# Power.net
KiCad netlist of a schematic drawn in Altium Designer
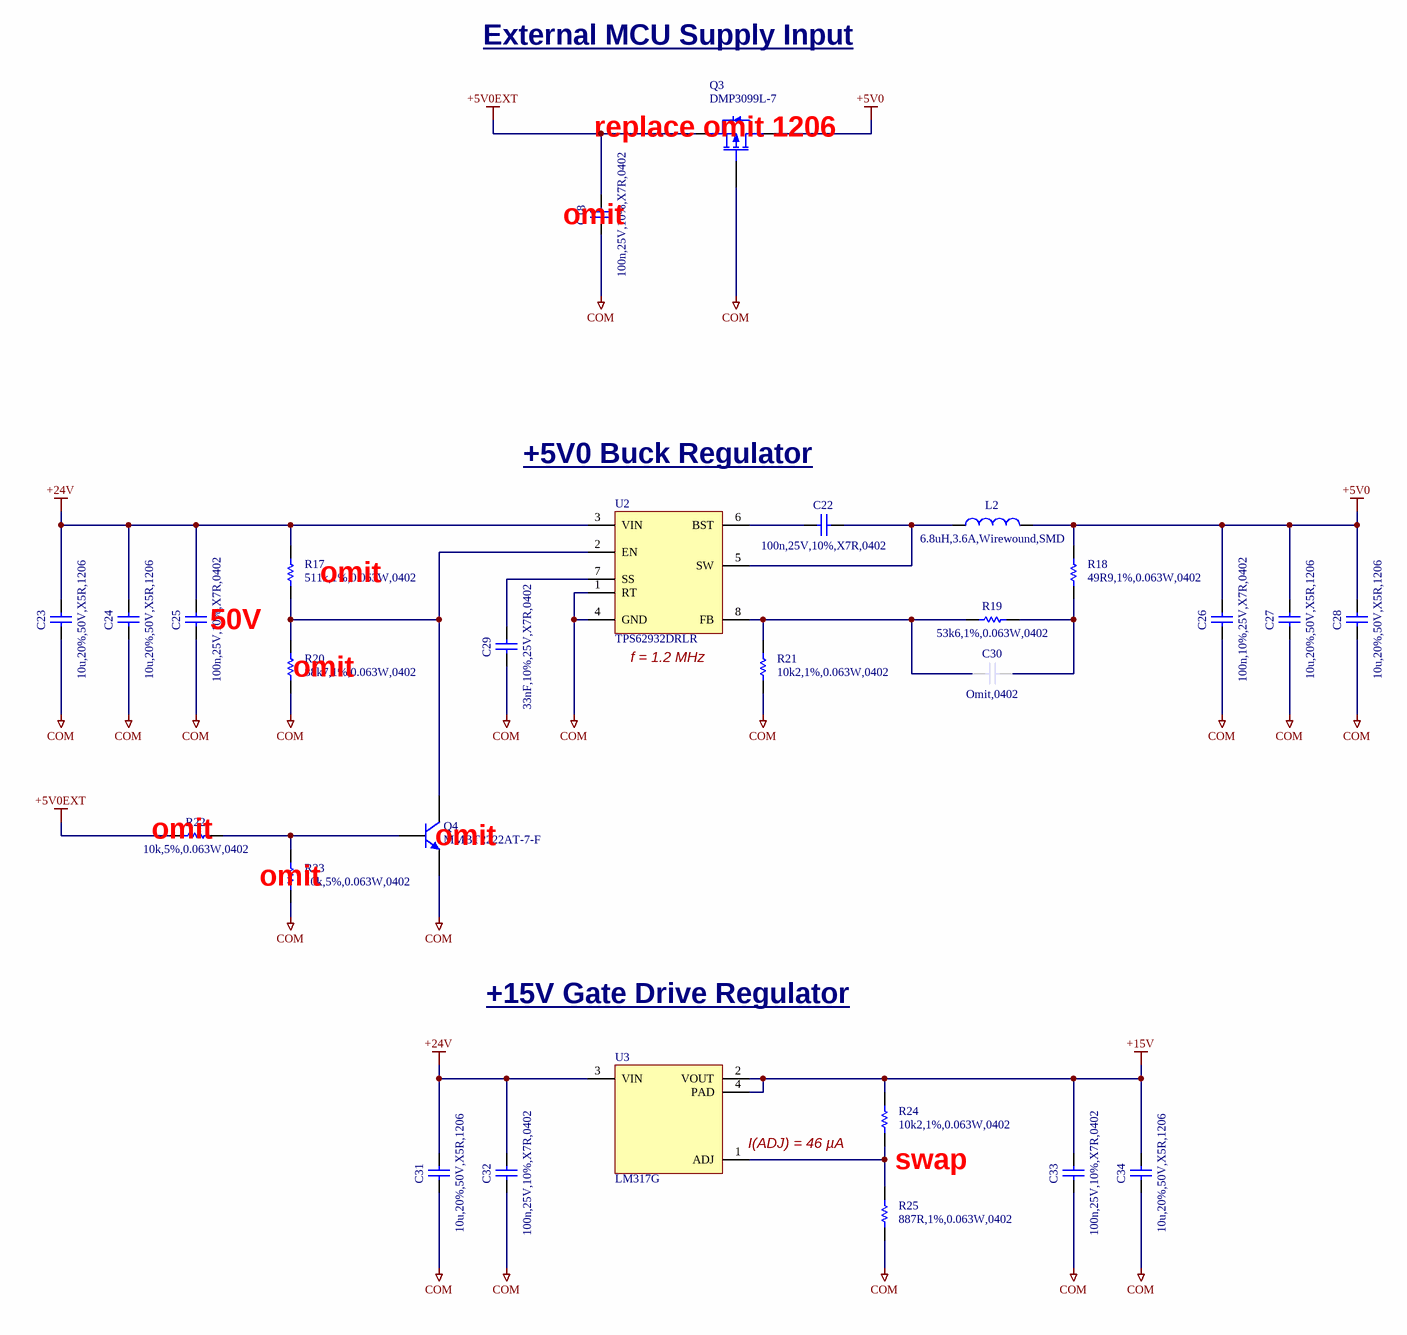
[diagram p0: Power.SchDoc]

(export (version "E")
  (design (tool "Eeschema 10.0.6"))
  (components
    (comp (ref "C18")
      (value "100n,25V,10%,X7R,0402")
      (footprint "CAPC1005X06N")
      (description "0.1ï¿½F ï¿½10% 25V Ceramic Capacitor X7R 0402 (1005 Metric)")
      (fields
        (field (name "MANUFACTURER 1 PART NUMBER") "GRM155R71E104KE14J")
        (field (name "VENDOR 1 PART NUMBER") "490-14603-1-ND")
        (field (name "CREATEDBY") "Judd Foster")
      )
      (libsource (lib "Component Library") (part "CAP,Cer,100nF,10%,25VDC,X7R,0402"))
    )
    (comp (ref "C22")
      (value "100n,25V,10%,X7R,0402")
      (footprint "CAPC1005X06N")
      (description "0.1ï¿½F ï¿½10% 25V Ceramic Capacitor X7R 0402 (1005 Metric)")
      (fields
        (field (name "MANUFACTURER 1 PART NUMBER") "GRM155R71E104KE14J")
        (field (name "VENDOR 1 PART NUMBER") "490-14603-1-ND")
        (field (name "CREATEDBY") "Judd Foster")
      )
      (libsource (lib "Component Library") (part "CAP,Cer,100nF,10%,25VDC,X7R,0402"))
    )
    (comp (ref "C23")
      (value "10u,20%,50V,X5R,1206")
      (footprint "CAPC3216X16N")
      (description "10ï¿½F ï¿½20% 50V Ceramic Capacitor X5R 1206 (3216 Metric)")
      (fields
        (field (name "MANUFACTURER 1 PART NUMBER") "CL31A106MBHNNNE")
        (field (name "VENDOR 1 PART NUMBER") "1276-6736-1-ND")
        (field (name "CREATEDBY") "Judd Foster")
      )
      (libsource (lib "Component Library") (part "CAP,Cer,10uF,50VDC,X5R,1206"))
    )
    (comp (ref "C24")
      (value "10u,20%,50V,X5R,1206")
      (footprint "CAPC3216X16N")
      (description "10ï¿½F ï¿½20% 50V Ceramic Capacitor X5R 1206 (3216 Metric)")
      (fields
        (field (name "MANUFACTURER 1 PART NUMBER") "CL31A106MBHNNNE")
        (field (name "VENDOR 1 PART NUMBER") "1276-6736-1-ND")
        (field (name "CREATEDBY") "Judd Foster")
      )
      (libsource (lib "Component Library") (part "CAP,Cer,10uF,50VDC,X5R,1206"))
    )
    (comp (ref "C25")
      (value "100n,25V,10%,X7R,0402")
      (footprint "CAPC1005X06N")
      (description "0.1ï¿½F ï¿½10% 25V Ceramic Capacitor X7R 0402 (1005 Metric)")
      (fields
        (field (name "MANUFACTURER 1 PART NUMBER") "GRM155R71E104KE14J")
        (field (name "VENDOR 1 PART NUMBER") "490-14603-1-ND")
        (field (name "CREATEDBY") "Judd Foster")
      )
      (libsource (lib "Component Library") (part "CAP,Cer,100nF,10%,25VDC,X7R,0402"))
    )
    (comp (ref "C26")
      (value "100n,10%,25V,X7R,0402")
      (footprint "CAPC1005X06N")
      (description "0.1ï¿½F ï¿½10% 25V Ceramic Capacitor X7R 0402 (1005 Metric)")
      (fields
        (field (name "MANUFACTURER 1 PART NUMBER") "GRM155R71E104KE14J")
        (field (name "VENDOR 1 PART NUMBER") "490-14603-1-ND")
        (field (name "CREATEDBY") "Judd Foster")
      )
      (libsource (lib "Component Library") (part "CAP,Cer,100nF,10%,25V,X7R,0402"))
    )
    (comp (ref "C27")
      (value "10u,20%,50V,X5R,1206")
      (footprint "CAPC3216X16N")
      (description "10ï¿½F ï¿½20% 50V Ceramic Capacitor X5R 1206 (3216 Metric)")
      (fields
        (field (name "MANUFACTURER 1 PART NUMBER") "CL31A106MBHNNNE")
        (field (name "VENDOR 1 PART NUMBER") "1276-6736-1-ND")
        (field (name "CREATEDBY") "Judd Foster")
      )
      (libsource (lib "Component Library") (part "CAP,Cer,10uF,50VDC,X5R,1206"))
    )
    (comp (ref "C28")
      (value "10u,20%,50V,X5R,1206")
      (footprint "CAPC3216X16N")
      (description "10ï¿½F ï¿½20% 50V Ceramic Capacitor X5R 1206 (3216 Metric)")
      (fields
        (field (name "MANUFACTURER 1 PART NUMBER") "CL31A106MBHNNNE")
        (field (name "VENDOR 1 PART NUMBER") "1276-6736-1-ND")
        (field (name "CREATEDBY") "Judd Foster")
      )
      (libsource (lib "Component Library") (part "CAP,Cer,10uF,50VDC,X5R,1206"))
    )
    (comp (ref "C29")
      (value "33nF,10%,25V,X7R,0402")
      (footprint "CAPC1005X06N")
      (description "0.033 ÂµF Â±10% 25V Ceramic Capacitor X7R 0402 (1005 Metric)")
      (fields
        (field (name "MANUFACTURER 1 PART NUMBER") "GRM155R71E333KA88D")
        (field (name "VENDOR 1 PART NUMBER") "490-3253-1-ND")
        (field (name "CREATEDBY") "Judd Foster")
      )
      (libsource (lib "Component Library") (part "CAP,Cer,33nF,10%,25V,X7R,0402"))
    )
    (comp (ref "C30")
      (value "Omit,0402")
      (footprint "CAPC1005X06N")
      (description "Omit")
      (fields (field (name "CREATEDBY") "Judd Foster"))
      (libsource (lib "Component Library") (part "CAP,Omit,0402"))
    )
    (comp (ref "C31")
      (value "10u,20%,50V,X5R,1206")
      (footprint "CAPC3216X16N")
      (description "10ï¿½F ï¿½20% 50V Ceramic Capacitor X5R 1206 (3216 Metric)")
      (fields
        (field (name "MANUFACTURER 1 PART NUMBER") "CL31A106MBHNNNE")
        (field (name "VENDOR 1 PART NUMBER") "1276-6736-1-ND")
        (field (name "CREATEDBY") "Judd Foster")
      )
      (libsource (lib "Component Library") (part "CAP,Cer,10uF,50VDC,X5R,1206"))
    )
    (comp (ref "C32")
      (value "100n,25V,10%,X7R,0402")
      (footprint "CAPC1005X06N")
      (description "0.1ï¿½F ï¿½10% 25V Ceramic Capacitor X7R 0402 (1005 Metric)")
      (fields
        (field (name "MANUFACTURER 1 PART NUMBER") "GRM155R71E104KE14J")
        (field (name "VENDOR 1 PART NUMBER") "490-14603-1-ND")
        (field (name "CREATEDBY") "Judd Foster")
      )
      (libsource (lib "Component Library") (part "CAP,Cer,100nF,10%,25VDC,X7R,0402"))
    )
    (comp (ref "C33")
      (value "100n,25V,10%,X7R,0402")
      (footprint "CAPC1005X06N")
      (description "0.1ï¿½F ï¿½10% 25V Ceramic Capacitor X7R 0402 (1005 Metric)")
      (fields
        (field (name "MANUFACTURER 1 PART NUMBER") "GRM155R71E104KE14J")
        (field (name "VENDOR 1 PART NUMBER") "490-14603-1-ND")
        (field (name "CREATEDBY") "Judd Foster")
      )
      (libsource (lib "Component Library") (part "CAP,Cer,100nF,10%,25VDC,X7R,0402"))
    )
    (comp (ref "C34")
      (value "10u,20%,50V,X5R,1206")
      (footprint "CAPC3216X16N")
      (description "10ï¿½F ï¿½20% 50V Ceramic Capacitor X5R 1206 (3216 Metric)")
      (fields
        (field (name "MANUFACTURER 1 PART NUMBER") "CL31A106MBHNNNE")
        (field (name "VENDOR 1 PART NUMBER") "1276-6736-1-ND")
        (field (name "CREATEDBY") "Judd Foster")
      )
      (libsource (lib "Component Library") (part "CAP,Cer,10uF,50VDC,X5R,1206"))
    )
    (comp (ref "L2")
      (value "6.8uH,3.6A,Wirewound,SMD")
      (footprint "BOURNS_SRN6045TA")
      (description "6.8 ÂµH Semi-Shielded Drum Core, Wirewound Inductor 3.6 A 34mOhm Nonstandard")
      (fields
        (field (name "MANUFACTURER 1 PART NUMBER") "SRN6045TA-6R8M")
        (field (name "VENDOR 1 PART NUMBER") "SRN6045TA-6R8MCT-ND")
        (field (name "CREATEDBY") "Judd Foster")
      )
      (libsource (lib "Component Library") (part "IND,6.8uH,3.6A,Wirewound,SMD"))
    )
    (comp (ref "Q3")
      (value "DMP3099L-7")
      (footprint "DIODES_SOT23")
      (description "P-Channel 30 V 3.8A (Ta) 1.08W (Ta) Surface Mount SOT-23-3")
      (fields
        (field (name "VENDOR 1 PART NUMBER") "DMP3099L-7DICT-ND")
        (field (name "CREATEDBY") "Judd Foster")
      )
      (libsource (lib "Component Library") (part "MOSFET,P Ch,30V,3.8A"))
    )
    (comp (ref "Q4")
      (value "MMBT2222AT-7-F")
      (footprint "SOTFL50P160X90-3N")
      (description "Bipolar (BJT) Transistor NPN 40 V 600 mA 300MHz 150 mW Surface Mount SOT-523")
      (fields
        (field (name "VENDOR 1 PART NUMBER") "MMBT2222AT-FDICT-ND")
        (field (name "CREATEDBY") "Judd Foster")
      )
      (libsource (lib "Component Library") (part "Trans,NPN,40V,600mA,SOT523"))
    )
    (comp (ref "R17")
      (value "511k,1%,0.063W,0402")
      (footprint "RESC1005X04N")
      (description "511 kOhms Â±1% 0.063W, 1/16W Chip Resistor 0402 (1005 Metric) Moisture Resistant Thick Film")
      (fields
        (field (name "MANUFACTURER 1 PART NUMBER") "RC0402FR-07511KL")
        (field (name "VENDOR 1 PART NUMBER") "YAG3176CT-ND")
        (field (name "CREATEDBY") "Judd Foster")
      )
      (libsource (lib "Component Library") (part "RES,511k,1%,0.063W,0402"))
    )
    (comp (ref "R18")
      (value "49R9,1%,0.063W,0402")
      (footprint "RESC1005X04N")
      (description "49.9 Ohms Â±1% 0.063W, 1/16W Chip Resistor 0402 (1005 Metric) Moisture Resistant Thick Film")
      (fields
        (field (name "MANUFACTURER 1 PART NUMBER") "RC0402FR-0749R9L")
        (field (name "VENDOR 1 PART NUMBER") "311-49.9LRCT-ND")
        (field (name "CREATEDBY") "Judd Foster")
      )
      (libsource (lib "Component Library") (part "RES,49R9,1%,0.063W,0402"))
    )
    (comp (ref "R19")
      (value "53k6,1%,0.063W,0402")
      (footprint "RESC1005X04N")
      (description "53.6 kOhms Â±1% 0.063W, 1/16W Chip Resistor 0402 (1005 Metric) Moisture Resistant Thick Film")
      (fields
        (field (name "MANUFACTURER 1 PART NUMBER") "RC0402FR-0753K6L")
        (field (name "VENDOR 1 PART NUMBER") "311-53.6KLRCT-ND")
        (field (name "CREATEDBY") "Judd Foster")
      )
      (libsource (lib "Component Library") (part "RES.53k6,1%,0.063W,0402"))
    )
    (comp (ref "R20")
      (value "88k7,1%,0.063W,0402")
      (footprint "RESC1005X04N")
      (fields
        (field (name "MANUFACTURER 1 PART NUMBER") "AC0402FR-0788K7L")
        (field (name "VENDOR 1 PART NUMBER") "13-AC0402FR-0788K7LCT-ND")
        (field (name "CREATEDBY") "Judd Foster")
      )
      (libsource (lib "Component Library") (part "RES,88k7,1%,0.063W,0402"))
    )
    (comp (ref "R21")
      (value "10k2,1%,0.063W,0402")
      (footprint "RESC1005X04N")
      (description "10.2 kOhms Â±1% 0.063W, 1/16W Chip Resistor 0402 (1005 Metric) Moisture Resistant Thick Film")
      (fields
        (field (name "MANUFACTURER 1 PART NUMBER") "RC0402FR-0710K2L")
        (field (name "VENDOR 1 PART NUMBER") "YAG2950CT-ND")
        (field (name "CREATEDBY") "Judd Foster")
      )
      (libsource (lib "Component Library") (part "RES,10k2,1%,0.063W,0402"))
    )
    (comp (ref "R22")
      (value "10k,5%,0.063W,0402")
      (footprint "RESC1005X04N")
      (description "10 kOhms ï¿½5% 0.063W, 1/16W Chip Resistor 0402 (1005 Metric) Automotive AEC-Q200 Thick Film")
      (fields
        (field (name "MANUFACTURER 1 PART NUMBER") "RMCF0402JT10K0")
        (field (name "VENDOR 1 PART NUMBER") "RMCF0402JT10K0CT-ND")
        (field (name "CREATEDBY") "Judd Foster")
      )
      (libsource (lib "Component Library") (part "RES,10k,5%,0.063W,0402"))
    )
    (comp (ref "R23")
      (value "10k,5%,0.063W,0402")
      (footprint "RESC1005X04N")
      (description "10 kOhms ï¿½5% 0.063W, 1/16W Chip Resistor 0402 (1005 Metric) Automotive AEC-Q200 Thick Film")
      (fields
        (field (name "MANUFACTURER 1 PART NUMBER") "RMCF0402JT10K0")
        (field (name "VENDOR 1 PART NUMBER") "RMCF0402JT10K0CT-ND")
        (field (name "CREATEDBY") "Judd Foster")
      )
      (libsource (lib "Component Library") (part "RES,10k,5%,0.063W,0402"))
    )
    (comp (ref "R24")
      (value "10k2,1%,0.063W,0402")
      (footprint "RESC1005X04N")
      (description "10.2 kOhms Â±1% 0.063W, 1/16W Chip Resistor 0402 (1005 Metric) Moisture Resistant Thick Film")
      (fields
        (field (name "MANUFACTURER 1 PART NUMBER") "RC0402FR-0710K2L")
        (field (name "VENDOR 1 PART NUMBER") "YAG2950CT-ND")
        (field (name "CREATEDBY") "Judd Foster")
      )
      (libsource (lib "Component Library") (part "RES,10k2,1%,0.063W,0402"))
    )
    (comp (ref "R25")
      (value "887R,1%,0.063W,0402")
      (footprint "RESC1005X04N")
      (description "887Î© 62.5mW 50V Â±200ppm/â„ƒ Â±1% Thick Film Resistors 0402 Chip Resistor - Surface Mount ROHS")
      (fields
        (field (name "MANUFACTURER 1 PART NUMBER") "RC-02W8870FT")
        (field (name "VENDOR 1 PART NUMBER") "C321640")
        (field (name "CREATEDBY") "Judd Foster")
      )
      (libsource (lib "Component Library") (part "RES,887R,1%,0.063W,0402"))
    )
    (comp (ref "U2")
      (value "TPS62932DRLR")
      (footprint "TEXASINSTRUMENTS_PKG_DRL0008A")
      (description "Buck Switching Regulator IC Positive Adjustable 0.8V 1 Output 2A SOT-583")
      (fields
        (field (name "VENDOR 1 PART NUMBER") "296-TPS62932DRLRCT-ND")
        (field (name "CREATEDBY") "Judd Foster")
      )
      (libsource (lib "Component Library") (part "TPS62932DRLR"))
    )
    (comp (ref "U3")
      (value "LM317G")
      (footprint "UMW_PKG_SOT223-3L")
      (fields (field (name "VENDOR 1 PART NUMBER") "C347367") (field (name "CREATEDBY") "Judd Foster"))
      (libsource (lib "Component Library") (part "LM317G"))
    )
  )
  (nets
    (net (code "1") (name "+5V0") (class "Default")
      (node (ref "C26") (pin "2") (pinfunction "2_2") (pintype "passive"))
      (node (ref "C27") (pin "2") (pinfunction "2_2") (pintype "passive"))
      (node (ref "C28") (pin "2") (pinfunction "2_2") (pintype "passive"))
      (node (ref "L2") (pin "2") (pinfunction "2_2") (pintype "passive"))
      (node (ref "Q3") (pin "3") (pinfunction "D_3") (pintype "passive"))
      (node (ref "R18") (pin "2") (pinfunction "2_2") (pintype "passive"))
    )
    (net (code "2") (name "+5V0EXT") (class "Default")
      (node (ref "C18") (pin "2") (pinfunction "2_2") (pintype "passive"))
      (node (ref "Q3") (pin "2") (pinfunction "S_2") (pintype "passive"))
      (node (ref "R22") (pin "2") (pinfunction "2_2") (pintype "passive"))
    )
    (net (code "3") (name "+15V") (class "Default")
      (node (ref "C33") (pin "2") (pinfunction "2_2") (pintype "passive"))
      (node (ref "C34") (pin "2") (pinfunction "2_2") (pintype "passive"))
      (node (ref "R24") (pin "2") (pinfunction "2_2") (pintype "passive"))
      (node (ref "U3") (pin "2") (pinfunction "VOUT_2") (pintype "power_in"))
      (node (ref "U3") (pin "4") (pinfunction "PAD_4") (pintype "power_in"))
    )
    (net (code "4") (name "+24V") (class "Default")
      (node (ref "C23") (pin "2") (pinfunction "2_2") (pintype "passive"))
      (node (ref "C24") (pin "2") (pinfunction "2_2") (pintype "passive"))
      (node (ref "C25") (pin "2") (pinfunction "2_2") (pintype "passive"))
      (node (ref "C31") (pin "2") (pinfunction "2_2") (pintype "passive"))
      (node (ref "C32") (pin "2") (pinfunction "2_2") (pintype "passive"))
      (node (ref "R17") (pin "2") (pinfunction "2_2") (pintype "passive"))
      (node (ref "U2") (pin "3") (pinfunction "VIN_3") (pintype "passive"))
      (node (ref "U3") (pin "3") (pinfunction "VIN_3") (pintype "power_in"))
    )
    (net (code "5") (name "COM") (class "Default")
      (node (ref "C18") (pin "1") (pinfunction "1_1") (pintype "passive"))
      (node (ref "C23") (pin "1") (pinfunction "1_1") (pintype "passive"))
      (node (ref "C24") (pin "1") (pinfunction "1_1") (pintype "passive"))
      (node (ref "C25") (pin "1") (pinfunction "1_1") (pintype "passive"))
      (node (ref "C26") (pin "1") (pinfunction "1_1") (pintype "passive"))
      (node (ref "C27") (pin "1") (pinfunction "1_1") (pintype "passive"))
      (node (ref "C28") (pin "1") (pinfunction "1_1") (pintype "passive"))
      (node (ref "C29") (pin "1") (pinfunction "1_1") (pintype "passive"))
      (node (ref "C31") (pin "1") (pinfunction "1_1") (pintype "passive"))
      (node (ref "C32") (pin "1") (pinfunction "1_1") (pintype "passive"))
      (node (ref "C33") (pin "1") (pinfunction "1_1") (pintype "passive"))
      (node (ref "C34") (pin "1") (pinfunction "1_1") (pintype "passive"))
      (node (ref "Q3") (pin "1") (pinfunction "G_1") (pintype "passive"))
      (node (ref "Q4") (pin "2") (pinfunction "E_2") (pintype "passive"))
      (node (ref "R20") (pin "1") (pinfunction "1_1") (pintype "passive"))
      (node (ref "R21") (pin "1") (pinfunction "1_1") (pintype "passive"))
      (node (ref "R23") (pin "2") (pinfunction "2_2") (pintype "passive"))
      (node (ref "R25") (pin "1") (pinfunction "1_1") (pintype "passive"))
      (node (ref "U2") (pin "1") (pinfunction "RT_1") (pintype "passive"))
      (node (ref "U2") (pin "4") (pinfunction "GND_4") (pintype "passive"))
    )
    (net (code "6") (name "Net-(C30-Pad2)") (class "Default")
      (node (ref "C30") (pin "2") (pinfunction "2_2") (pintype "passive"))
      (node (ref "R18") (pin "1") (pinfunction "1_1") (pintype "passive"))
      (node (ref "R19") (pin "1") (pinfunction "1_1") (pintype "passive"))
    )
    (net (code "7") (name "Net-(Q4-B)") (class "Default")
      (node (ref "Q4") (pin "1") (pinfunction "B_1") (pintype "passive"))
      (node (ref "R22") (pin "1") (pinfunction "1_1") (pintype "passive"))
      (node (ref "R23") (pin "1") (pinfunction "1_1") (pintype "passive"))
    )
    (net (code "8") (name "Net-(Q4-C)") (class "Default")
      (node (ref "Q4") (pin "3") (pinfunction "C_3") (pintype "passive"))
      (node (ref "R17") (pin "1") (pinfunction "1_1") (pintype "passive"))
      (node (ref "R20") (pin "2") (pinfunction "2_2") (pintype "passive"))
      (node (ref "U2") (pin "2") (pinfunction "EN_2") (pintype "passive"))
    )
    (net (code "9") (name "Net-(U2-BST)") (class "Default")
      (node (ref "C22") (pin "2") (pinfunction "2_2") (pintype "passive"))
      (node (ref "U2") (pin "6") (pinfunction "BST_6") (pintype "passive"))
    )
    (net (code "10") (name "Net-(U2-FB)") (class "Default")
      (node (ref "C30") (pin "1") (pinfunction "1_1") (pintype "passive"))
      (node (ref "R19") (pin "2") (pinfunction "2_2") (pintype "passive"))
      (node (ref "R21") (pin "2") (pinfunction "2_2") (pintype "passive"))
      (node (ref "U2") (pin "8") (pinfunction "FB_8") (pintype "passive"))
    )
    (net (code "11") (name "Net-(U2-SS)") (class "Default")
      (node (ref "C29") (pin "2") (pinfunction "2_2") (pintype "passive"))
      (node (ref "U2") (pin "7") (pinfunction "SS_7") (pintype "passive"))
    )
    (net (code "12") (name "Net-(U2-SW)") (class "Default")
      (node (ref "C22") (pin "1") (pinfunction "1_1") (pintype "passive"))
      (node (ref "L2") (pin "1") (pinfunction "1_1") (pintype "passive"))
      (node (ref "U2") (pin "5") (pinfunction "SW_5") (pintype "passive"))
    )
    (net (code "13") (name "Net-(U3-ADJ)") (class "Default")
      (node (ref "R24") (pin "1") (pinfunction "1_1") (pintype "passive"))
      (node (ref "R25") (pin "2") (pinfunction "2_2") (pintype "passive"))
      (node (ref "U3") (pin "1") (pinfunction "ADJ_1") (pintype "power_in"))
    )
  )
)
